# DC_DC_Converter_rev1.net
KiCad netlist of a schematic drawn in EAGLE
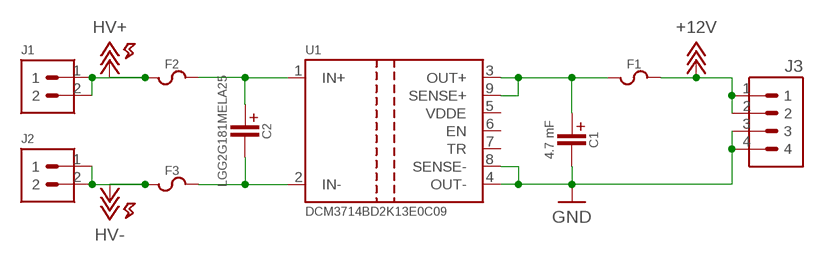
[diagram p0: schematic, sheet 1]

(export (version "E")
  (design (tool "Eeschema 10.0.6"))
  (components
    (comp (ref "C1")
      (value "4.7 mF")
      (footprint "eagle-import:EKYC_MM")
      (libsource (lib "eagle-import") (part "EKYC250E__622MM25S"))
    )
    (comp (ref "C2")
      (value "LGG2G181MELA25")
      (footprint "eagle-import:L_A")
      (libsource (lib "eagle-import") (part "LGG2G181MELA25"))
    )
    (comp (ref "F1")
      (value "FUSE_MINIBLADE")
      (footprint "eagle-import:MINI-BLADE_FUSE_HOLDER")
      (libsource (lib "eagle-import") (part "FUSE_MINIBLADE"))
    )
    (comp (ref "F2")
      (value "885_FUSE")
      (footprint "eagle-import:0885")
      (libsource (lib "eagle-import") (part "885_FUSE"))
    )
    (comp (ref "F3")
      (value "885_FUSE")
      (footprint "eagle-import:0885")
      (libsource (lib "eagle-import") (part "885_FUSE"))
    )
    (comp (ref "J1")
      (value "CONNECTOR-2")
      (footprint "eagle-import:MOLEX_NANOFIT_PTH_02")
      (fields (field (name "MPN") "1053091202"))
      (libsource (lib "eagle-import") (part "CONNECTOR-2"))
    )
    (comp (ref "J2")
      (value "CONNECTOR-2")
      (footprint "eagle-import:MOLEX_NANOFIT_PTH_02")
      (fields (field (name "MPN") "1053091202"))
      (libsource (lib "eagle-import") (part "CONNECTOR-2"))
    )
    (comp (ref "J3")
      (value "CONNECTOR-4MINIFIT")
      (footprint "eagle-import:MOLEX_MINIFIT_PTH_04")
      (libsource (lib "eagle-import") (part "CONNECTOR-4MINIFIT"))
    )
    (comp (ref "U1")
      (value "DCM3714BD2K13E0C09")
      (footprint "eagle-import:3714DCM_VIA")
      (libsource (lib "eagle-import") (part "DCM3714BD2K13E0C09"))
    )
  )
  (nets
    (net (code "1") (name "+12V") (class "Default")
      (node (ref "F1") (pin "R1") (pinfunction "2_R1") (pintype "passive"))
      (node (ref "F1") (pin "R2") (pinfunction "2_R2") (pintype "passive"))
      (node (ref "J3") (pin "1") (pinfunction "1_1") (pintype "passive"))
      (node (ref "J3") (pin "2") (pinfunction "2_2") (pintype "passive"))
    )
    (net (code "2") (name "/VDDE") (class "Default")
      (node (ref "U1") (pin "5") (pinfunction "VDDE_5") (pintype "power_in"))
    )
    (net (code "3") (name "GND") (class "Default")
      (node (ref "C1") (pin "-") (pinfunction "MINUS_-") (pintype "passive"))
      (node (ref "J3") (pin "3") (pinfunction "3_3") (pintype "passive"))
      (node (ref "J3") (pin "4") (pinfunction "4_4") (pintype "passive"))
      (node (ref "U1") (pin "4") (pinfunction "OUT-_4") (pintype "power_in"))
      (node (ref "U1") (pin "8") (pinfunction "SENSE-_8") (pintype "input"))
    )
    (net (code "4") (name "HV+") (class "Default")
      (node (ref "F2") (pin "1") (pinfunction "1_1") (pintype "passive"))
      (node (ref "J1") (pin "1") (pinfunction "1_1") (pintype "passive"))
      (node (ref "J1") (pin "2") (pinfunction "2_2") (pintype "passive"))
    )
    (net (code "5") (name "HV-") (class "Default")
      (node (ref "F3") (pin "1") (pinfunction "1_1") (pintype "passive"))
      (node (ref "J2") (pin "1") (pinfunction "1_1") (pintype "passive"))
      (node (ref "J2") (pin "2") (pinfunction "2_2") (pintype "passive"))
    )
    (net (code "6") (name "Net-(C1-PLUS)") (class "Default")
      (node (ref "C1") (pin "+") (pinfunction "PLUS_+") (pintype "passive"))
      (node (ref "F1") (pin "L1") (pinfunction "1_L1") (pintype "passive"))
      (node (ref "F1") (pin "L2") (pinfunction "1_L2") (pintype "passive"))
      (node (ref "U1") (pin "3") (pinfunction "OUT+_3") (pintype "power_in"))
      (node (ref "U1") (pin "9") (pinfunction "SENSE+_9") (pintype "input"))
    )
    (net (code "7") (name "Net-(C2-MINUS)") (class "Default")
      (node (ref "C2") (pin "-") (pinfunction "MINUS_-") (pintype "passive"))
      (node (ref "F3") (pin "2") (pinfunction "2_2") (pintype "passive"))
      (node (ref "U1") (pin "2") (pinfunction "IN-_2") (pintype "power_in"))
    )
    (net (code "8") (name "Net-(C2-PLUS)") (class "Default")
      (node (ref "C2") (pin "+") (pinfunction "PLUS_+") (pintype "passive"))
      (node (ref "F2") (pin "2") (pinfunction "2_2") (pintype "passive"))
      (node (ref "U1") (pin "1") (pinfunction "IN+_1") (pintype "power_in"))
    )
    (net (code "9") (name "unconnected-(U1-EN-Pad6)") (class "Default")
      (node (ref "U1") (pin "6") (pinfunction "EN_6") (pintype "input"))
    )
    (net (code "10") (name "unconnected-(U1-TR-Pad7)") (class "Default")
      (node (ref "U1") (pin "7") (pinfunction "TR_7") (pintype "input"))
    )
  )
)
